# fedpower_mic841_revf.net
KiCad netlist of a schematic drawn in EAGLE
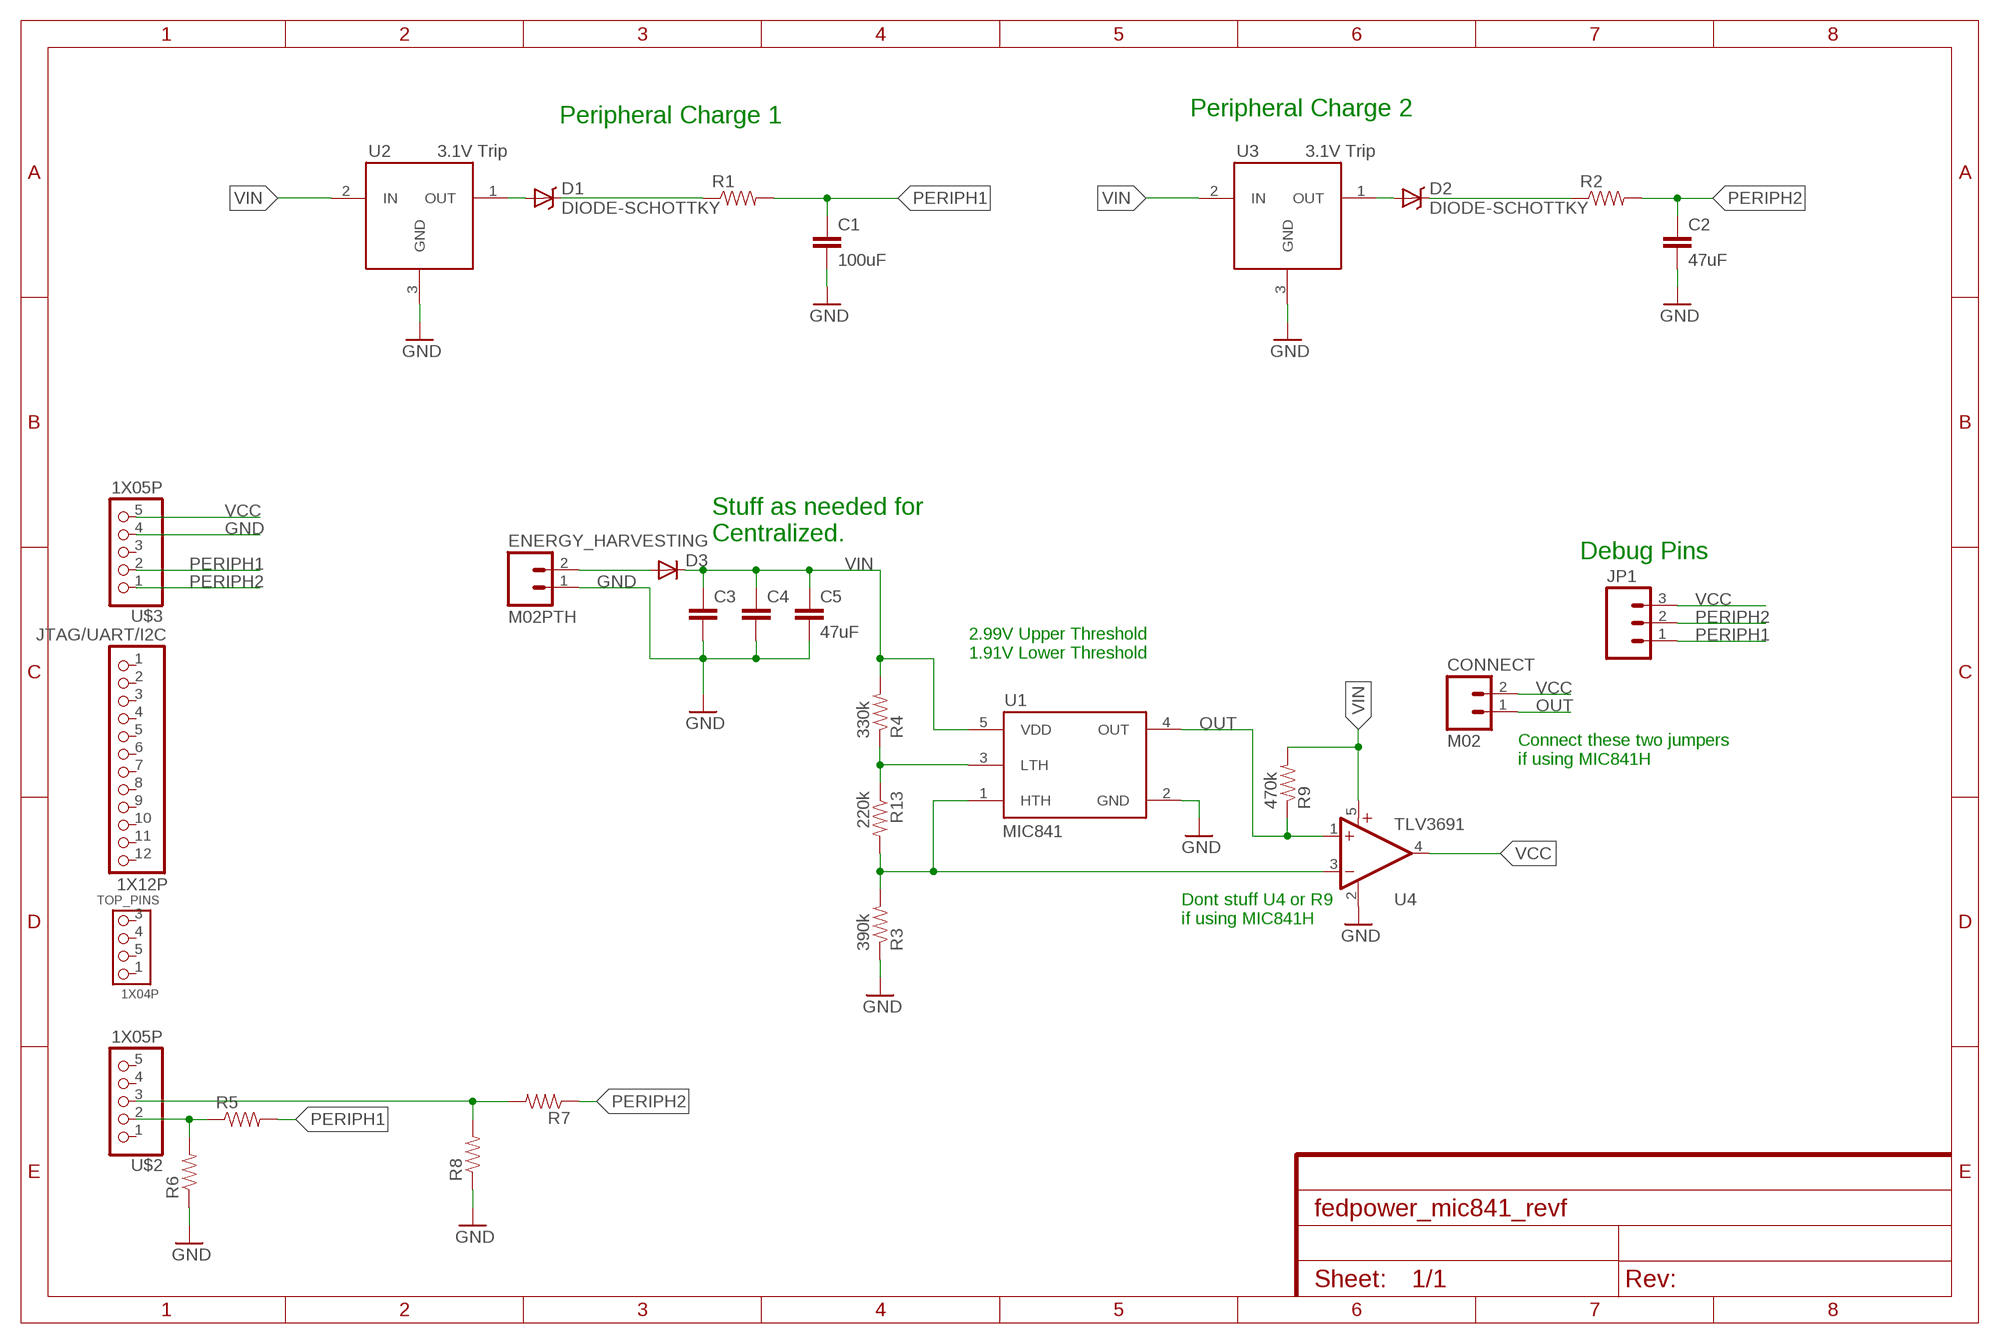
[diagram p0: schematic, sheet 1]

(export (version "E")
  (design (tool "Eeschema 10.0.6"))
  (components
    (comp (ref "C1")
      (value "100uF")
      (footprint "eagle-import:0805")
      (libsource (lib "eagle-import") (part "1.0UF-25V-+80/-20(0805)"))
    )
    (comp (ref "C2")
      (value "47uF")
      (footprint "eagle-import:0805")
      (libsource (lib "eagle-import") (part "1.0UF-25V-+80/-20(0805)"))
    )
    (comp (ref "C3")
      (value "1.0UF-25V-+80/-20(0805)")
      (footprint "eagle-import:0805")
      (libsource (lib "eagle-import") (part "1.0UF-25V-+80/-20(0805)"))
    )
    (comp (ref "C4")
      (value "1.0UF-25V-+80/-20(0805)")
      (footprint "eagle-import:0805")
      (libsource (lib "eagle-import") (part "1.0UF-25V-+80/-20(0805)"))
    )
    (comp (ref "C5")
      (value "47uF")
      (footprint "eagle-import:0805")
      (libsource (lib "eagle-import") (part "1.0UF-25V-+80/-20(0805)"))
    )
    (comp (ref "CONNECT")
      (value "M02")
      (footprint "eagle-import:1X02-1.27MM")
      (libsource (lib "eagle-import") (part "M02"))
    )
    (comp (ref "D1")
      (value "DIODE-SCHOTTKY")
      (footprint "eagle-import:SOD-323")
      (libsource (lib "eagle-import") (part "DIODE-SCHOTTKY"))
    )
    (comp (ref "D2")
      (value "DIODE-SCHOTTKY")
      (footprint "eagle-import:SOD-323")
      (libsource (lib "eagle-import") (part "DIODE-SCHOTTKY"))
    )
    (comp (ref "D3")
      (value "DIODESOD")
      (footprint "eagle-import:SOD-323")
      (libsource (lib "eagle-import") (part "DIODESOD"))
    )
    (comp (ref "ENERGY_HARVESTING")
      (value "M02PTH")
      (footprint "eagle-import:1X02")
      (libsource (lib "eagle-import") (part "M02PTH"))
    )
    (comp (ref "JP1")
      (value "M03PTH")
      (footprint "eagle-import:1X03")
      (libsource (lib "eagle-import") (part "M03PTH"))
    )
    (comp (ref "JTAG/UART/I2C")
      (value "1X12P")
      (footprint "eagle-import:1X12P")
      (libsource (lib "eagle-import") (part "1X12P"))
    )
    (comp (ref "R1")
      (value "0.3OHM-1/8W-1%(0805)")
      (footprint "eagle-import:0805")
      (libsource (lib "eagle-import") (part "0.3OHM-1/8W-1%(0805)"))
    )
    (comp (ref "R2")
      (value "0.3OHM-1/8W-1%(0805)")
      (footprint "eagle-import:0805")
      (libsource (lib "eagle-import") (part "0.3OHM-1/8W-1%(0805)"))
    )
    (comp (ref "R3")
      (value "390k")
      (footprint "eagle-import:0805")
      (libsource (lib "eagle-import") (part "0.3OHM-1/8W-1%(0805)"))
    )
    (comp (ref "R4")
      (value "330k")
      (footprint "eagle-import:0805")
      (libsource (lib "eagle-import") (part "0.3OHM-1/8W-1%(0805)"))
    )
    (comp (ref "R5")
      (value "0.3OHM-1/8W-1%(0805)")
      (footprint "eagle-import:0805")
      (libsource (lib "eagle-import") (part "0.3OHM-1/8W-1%(0805)"))
    )
    (comp (ref "R6")
      (value "0.3OHM-1/8W-1%(0805)")
      (footprint "eagle-import:0805")
      (libsource (lib "eagle-import") (part "0.3OHM-1/8W-1%(0805)"))
    )
    (comp (ref "R7")
      (value "0.3OHM-1/8W-1%(0805)")
      (footprint "eagle-import:0805")
      (libsource (lib "eagle-import") (part "0.3OHM-1/8W-1%(0805)"))
    )
    (comp (ref "R8")
      (value "0.3OHM-1/8W-1%(0805)")
      (footprint "eagle-import:0805")
      (libsource (lib "eagle-import") (part "0.3OHM-1/8W-1%(0805)"))
    )
    (comp (ref "R9")
      (value "470k")
      (footprint "eagle-import:0805")
      (libsource (lib "eagle-import") (part "0.3OHM-1/8W-1%(0805)"))
    )
    (comp (ref "R13")
      (value "220k")
      (footprint "eagle-import:0805")
      (libsource (lib "eagle-import") (part "0.3OHM-1/8W-1%(0805)"))
    )
    (comp (ref "TOP_PINS")
      (value "1X04P")
      (footprint "eagle-import:1X04P")
      (libsource (lib "eagle-import") (part "1X04P"))
    )
    (comp (ref "U$2")
      (value "1X05P")
      (footprint "eagle-import:1X05P")
      (libsource (lib "eagle-import") (part "1X05P"))
    )
    (comp (ref "U$3")
      (value "1X05P")
      (footprint "eagle-import:1X05P")
      (libsource (lib "eagle-import") (part "1X05P"))
    )
    (comp (ref "U1")
      (value "MIC841")
      (footprint "eagle-import:SC70-5")
      (libsource (lib "eagle-import") (part "MIC841"))
    )
    (comp (ref "U2")
      (value "3.1V Trip")
      (footprint "eagle-import:SOT-23-5_1PRIMARY")
      (libsource (lib "eagle-import") (part "NCP300{dblquote}"))
    )
    (comp (ref "U3")
      (value "3.1V Trip")
      (footprint "eagle-import:SOT-23-5_1PRIMARY")
      (libsource (lib "eagle-import") (part "NCP300{dblquote}"))
    )
    (comp (ref "U4")
      (value "TLV3691")
      (footprint "eagle-import:SC70-5")
      (libsource (lib "eagle-import") (part "TLV3691"))
    )
  )
  (nets
    (net (code "1") (name "/OUT") (class "Default")
      (node (ref "CONNECT") (pin "1") (pinfunction "1_1") (pintype "passive"))
      (node (ref "R9") (pin "1") (pinfunction "1_1") (pintype "passive"))
      (node (ref "U1") (pin "4") (pinfunction "OUT_4") (pintype "bidirectional"))
      (node (ref "U4") (pin "1") (pinfunction "+IN_1") (pintype "input"))
    )
    (net (code "2") (name "GND") (class "Default")
      (node (ref "C1") (pin "2") (pinfunction "2_2") (pintype "passive"))
      (node (ref "C2") (pin "2") (pinfunction "2_2") (pintype "passive"))
      (node (ref "C3") (pin "2") (pinfunction "2_2") (pintype "passive"))
      (node (ref "C4") (pin "2") (pinfunction "2_2") (pintype "passive"))
      (node (ref "C5") (pin "2") (pinfunction "2_2") (pintype "passive"))
      (node (ref "ENERGY_HARVESTING") (pin "1") (pinfunction "1_1") (pintype "passive"))
      (node (ref "R3") (pin "1") (pinfunction "1_1") (pintype "passive"))
      (node (ref "R6") (pin "1") (pinfunction "1_1") (pintype "passive"))
      (node (ref "R8") (pin "1") (pinfunction "1_1") (pintype "passive"))
      (node (ref "U$3") (pin "4") (pinfunction "4_4") (pintype "passive"))
      (node (ref "U1") (pin "2") (pinfunction "GND_2") (pintype "bidirectional"))
      (node (ref "U2") (pin "3") (pinfunction "GND_3") (pintype "bidirectional"))
      (node (ref "U3") (pin "3") (pinfunction "GND_3") (pintype "bidirectional"))
      (node (ref "U4") (pin "2") (pinfunction "GND_2") (pintype "power_in"))
    )
    (net (code "3") (name "Net-(D1-A)") (class "Default")
      (node (ref "D1") (pin "2") (pinfunction "A_2") (pintype "passive"))
      (node (ref "U2") (pin "1") (pinfunction "OUT_1") (pintype "bidirectional"))
    )
    (net (code "4") (name "Net-(D1-C)") (class "Default")
      (node (ref "D1") (pin "1") (pinfunction "C_1") (pintype "passive"))
      (node (ref "R1") (pin "1") (pinfunction "1_1") (pintype "passive"))
    )
    (net (code "5") (name "Net-(D2-A)") (class "Default")
      (node (ref "D2") (pin "2") (pinfunction "A_2") (pintype "passive"))
      (node (ref "U3") (pin "1") (pinfunction "OUT_1") (pintype "bidirectional"))
    )
    (net (code "6") (name "Net-(D2-C)") (class "Default")
      (node (ref "D2") (pin "1") (pinfunction "C_1") (pintype "passive"))
      (node (ref "R2") (pin "1") (pinfunction "1_1") (pintype "passive"))
    )
    (net (code "7") (name "Net-(D3-A)") (class "Default")
      (node (ref "D3") (pin "2") (pinfunction "A_2") (pintype "passive"))
      (node (ref "ENERGY_HARVESTING") (pin "2") (pinfunction "2_2") (pintype "passive"))
    )
    (net (code "8") (name "Net-(R5-Pad1)") (class "Default")
      (node (ref "R5") (pin "1") (pinfunction "1_1") (pintype "passive"))
      (node (ref "R6") (pin "2") (pinfunction "2_2") (pintype "passive"))
      (node (ref "U$2") (pin "2") (pinfunction "2_2") (pintype "passive"))
    )
    (net (code "9") (name "Net-(R7-Pad2)") (class "Default")
      (node (ref "R7") (pin "2") (pinfunction "2_2") (pintype "passive"))
      (node (ref "R8") (pin "2") (pinfunction "2_2") (pintype "passive"))
      (node (ref "U$2") (pin "3") (pinfunction "3_3") (pintype "passive"))
    )
    (net (code "10") (name "Net-(U1-HTH)") (class "Default")
      (node (ref "R13") (pin "2") (pinfunction "2_2") (pintype "passive"))
      (node (ref "R3") (pin "2") (pinfunction "2_2") (pintype "passive"))
      (node (ref "U1") (pin "1") (pinfunction "HTH_1") (pintype "bidirectional"))
      (node (ref "U4") (pin "3") (pinfunction "-IN_3") (pintype "input"))
    )
    (net (code "11") (name "Net-(U1-LTH)") (class "Default")
      (node (ref "R13") (pin "1") (pinfunction "1_1") (pintype "passive"))
      (node (ref "R4") (pin "1") (pinfunction "1_1") (pintype "passive"))
      (node (ref "U1") (pin "3") (pinfunction "LTH_3") (pintype "bidirectional"))
    )
    (net (code "12") (name "PERIPH1") (class "Default")
      (node (ref "C1") (pin "1") (pinfunction "1_1") (pintype "passive"))
      (node (ref "JP1") (pin "1") (pinfunction "1_1") (pintype "passive"))
      (node (ref "R1") (pin "2") (pinfunction "2_2") (pintype "passive"))
      (node (ref "R5") (pin "2") (pinfunction "2_2") (pintype "passive"))
      (node (ref "U$3") (pin "2") (pinfunction "2_2") (pintype "passive"))
    )
    (net (code "13") (name "PERIPH2") (class "Default")
      (node (ref "C2") (pin "1") (pinfunction "1_1") (pintype "passive"))
      (node (ref "JP1") (pin "2") (pinfunction "2_2") (pintype "passive"))
      (node (ref "R2") (pin "2") (pinfunction "2_2") (pintype "passive"))
      (node (ref "R7") (pin "1") (pinfunction "1_1") (pintype "passive"))
      (node (ref "U$3") (pin "1") (pinfunction "1_1") (pintype "passive"))
    )
    (net (code "14") (name "VCC") (class "Default")
      (node (ref "CONNECT") (pin "2") (pinfunction "2_2") (pintype "passive"))
      (node (ref "JP1") (pin "3") (pinfunction "3_3") (pintype "passive"))
      (node (ref "U$3") (pin "5") (pinfunction "5_5") (pintype "passive"))
      (node (ref "U4") (pin "4") (pinfunction "OUT_4") (pintype "output"))
    )
    (net (code "15") (name "VIN") (class "Default")
      (node (ref "C3") (pin "1") (pinfunction "1_1") (pintype "passive"))
      (node (ref "C4") (pin "1") (pinfunction "1_1") (pintype "passive"))
      (node (ref "C5") (pin "1") (pinfunction "1_1") (pintype "passive"))
      (node (ref "D3") (pin "1") (pinfunction "C_1") (pintype "passive"))
      (node (ref "R4") (pin "2") (pinfunction "2_2") (pintype "passive"))
      (node (ref "R9") (pin "2") (pinfunction "2_2") (pintype "passive"))
      (node (ref "U1") (pin "5") (pinfunction "VDD_5") (pintype "bidirectional"))
      (node (ref "U2") (pin "2") (pinfunction "IN_2") (pintype "bidirectional"))
      (node (ref "U3") (pin "2") (pinfunction "IN_2") (pintype "bidirectional"))
      (node (ref "U4") (pin "5") (pinfunction "V+_5") (pintype "power_in"))
    )
    (net (code "16") (name "unconnected-(JTAG/UART/I2C-P$1-Pad1)") (class "Default")
      (node (ref "JTAG/UART/I2C") (pin "1") (pinfunction "P$1_1") (pintype "passive"))
    )
    (net (code "17") (name "unconnected-(JTAG/UART/I2C-P$2-Pad2)") (class "Default")
      (node (ref "JTAG/UART/I2C") (pin "2") (pinfunction "P$2_2") (pintype "passive"))
    )
    (net (code "18") (name "unconnected-(JTAG/UART/I2C-P$3-Pad3)") (class "Default")
      (node (ref "JTAG/UART/I2C") (pin "3") (pinfunction "P$3_3") (pintype "passive"))
    )
    (net (code "19") (name "unconnected-(JTAG/UART/I2C-P$4-Pad4)") (class "Default")
      (node (ref "JTAG/UART/I2C") (pin "4") (pinfunction "P$4_4") (pintype "passive"))
    )
    (net (code "20") (name "unconnected-(JTAG/UART/I2C-P$5-Pad5)") (class "Default")
      (node (ref "JTAG/UART/I2C") (pin "5") (pinfunction "P$5_5") (pintype "passive"))
    )
    (net (code "21") (name "unconnected-(JTAG/UART/I2C-P$6-Pad6)") (class "Default")
      (node (ref "JTAG/UART/I2C") (pin "6") (pinfunction "P$6_6") (pintype "passive"))
    )
    (net (code "22") (name "unconnected-(JTAG/UART/I2C-P$7-Pad7)") (class "Default")
      (node (ref "JTAG/UART/I2C") (pin "7") (pinfunction "P$7_7") (pintype "passive"))
    )
    (net (code "23") (name "unconnected-(JTAG/UART/I2C-P$8-Pad8)") (class "Default")
      (node (ref "JTAG/UART/I2C") (pin "8") (pinfunction "P$8_8") (pintype "passive"))
    )
    (net (code "24") (name "unconnected-(JTAG/UART/I2C-P$9-Pad9)") (class "Default")
      (node (ref "JTAG/UART/I2C") (pin "9") (pinfunction "P$9_9") (pintype "passive"))
    )
    (net (code "25") (name "unconnected-(JTAG/UART/I2C-P$10-Pad10)") (class "Default")
      (node (ref "JTAG/UART/I2C") (pin "10") (pinfunction "P$10_10") (pintype "passive"))
    )
    (net (code "26") (name "unconnected-(JTAG/UART/I2C-P$11-Pad11)") (class "Default")
      (node (ref "JTAG/UART/I2C") (pin "11") (pinfunction "P$11_11") (pintype "passive"))
    )
    (net (code "27") (name "unconnected-(JTAG/UART/I2C-P$12-Pad12)") (class "Default")
      (node (ref "JTAG/UART/I2C") (pin "12") (pinfunction "P$12_12") (pintype "passive"))
    )
    (net (code "28") (name "unconnected-(TOP_PINS-P$1-Pad3)") (class "Default")
      (node (ref "TOP_PINS") (pin "3") (pinfunction "P$1_3") (pintype "passive"))
    )
    (net (code "29") (name "unconnected-(TOP_PINS-P$2-Pad4)") (class "Default")
      (node (ref "TOP_PINS") (pin "4") (pinfunction "P$2_4") (pintype "passive"))
    )
    (net (code "30") (name "unconnected-(TOP_PINS-P$3-Pad5)") (class "Default")
      (node (ref "TOP_PINS") (pin "5") (pinfunction "P$3_5") (pintype "passive"))
    )
    (net (code "31") (name "unconnected-(TOP_PINS-P$4-Pad1)") (class "Default")
      (node (ref "TOP_PINS") (pin "1") (pinfunction "P$4_1") (pintype "passive"))
    )
    (net (code "32") (name "unconnected-(U$2-Pad1)") (class "Default")
      (node (ref "U$2") (pin "1") (pinfunction "1_1") (pintype "passive"))
    )
    (net (code "33") (name "unconnected-(U$2-Pad4)") (class "Default")
      (node (ref "U$2") (pin "4") (pinfunction "4_4") (pintype "passive"))
    )
    (net (code "34") (name "unconnected-(U$2-Pad5)") (class "Default")
      (node (ref "U$2") (pin "5") (pinfunction "5_5") (pintype "passive"))
    )
    (net (code "35") (name "unconnected-(U$3-Pad3)") (class "Default")
      (node (ref "U$3") (pin "3") (pinfunction "3_3") (pintype "passive"))
    )
    (net (code "36") (name "unconnected-(U2-NC-Pad4)") (class "Default")
      (node (ref "U2") (pin "4") (pinfunction "NC_4") (pintype "no_connect"))
    )
    (net (code "37") (name "unconnected-(U2-NC-Pad5)") (class "Default")
      (node (ref "U2") (pin "5") (pinfunction "NC_5") (pintype "no_connect"))
    )
    (net (code "38") (name "unconnected-(U3-NC-Pad4)") (class "Default")
      (node (ref "U3") (pin "4") (pinfunction "NC_4") (pintype "no_connect"))
    )
    (net (code "39") (name "unconnected-(U3-NC-Pad5)") (class "Default")
      (node (ref "U3") (pin "5") (pinfunction "NC_5") (pintype "no_connect"))
    )
  )
)
